# POEREG.net
KiCad netlist of a schematic drawn in EAGLE
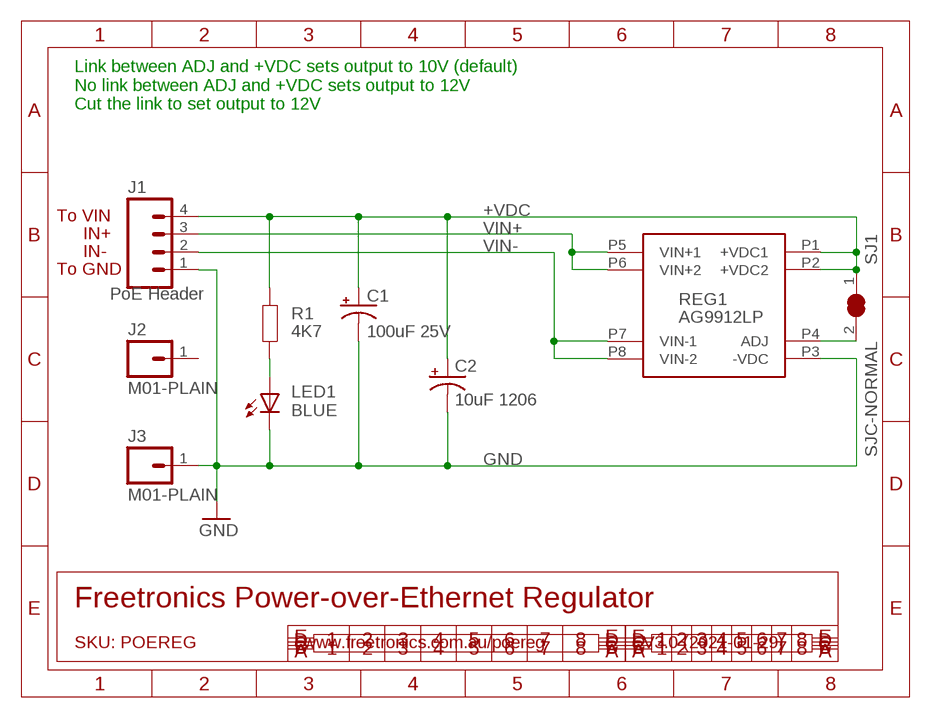
[diagram p0: schematic, sheet 1]

(export (version "E")
  (design (tool "Eeschema 10.0.6"))
  (components
    (comp (ref "C1")
      (value "100uF 25V")
      (footprint "eagle-import:PANASONIC_D")
      (libsource (lib "eagle-import") (part "CAP_POLD"))
    )
    (comp (ref "C2")
      (value "10uF 1206")
      (footprint "eagle-import:EIA3216")
      (libsource (lib "eagle-import") (part "CAP_POL1206"))
    )
    (comp (ref "J1")
      (value "PoE Header")
      (footprint "eagle-import:1X04")
      (libsource (lib "eagle-import") (part "M04-PLAIN"))
    )
    (comp (ref "J2")
      (value "M01-PLAIN")
      (footprint "eagle-import:1X01")
      (libsource (lib "eagle-import") (part "M01-PLAIN"))
    )
    (comp (ref "J3")
      (value "M01-PLAIN")
      (footprint "eagle-import:1X01")
      (libsource (lib "eagle-import") (part "M01-PLAIN"))
    )
    (comp (ref "LED1")
      (value "BLUE")
      (footprint "eagle-import:LED-0603")
      (libsource (lib "eagle-import") (part "LED0603"))
    )
    (comp (ref "R1")
      (value "4K7")
      (footprint "eagle-import:R0603")
      (libsource (lib "eagle-import") (part "RESISTOR0603"))
    )
    (comp (ref "REG1")
      (value "AG9912LP")
      (footprint "eagle-import:AG9900LP")
      (libsource (lib "eagle-import") (part "AG9900-LP"))
    )
    (comp (ref "SJ1")
      (value "SJC-NORMAL")
      (footprint "eagle-import:SJC")
      (libsource (lib "eagle-import") (part "SJC-NORMAL"))
    )
  )
  (nets
    (net (code "1") (name "/+VDC") (class "Default")
      (node (ref "C1") (pin "+") (pinfunction "+_+") (pintype "passive"))
      (node (ref "C2") (pin "A") (pinfunction "+_A") (pintype "passive"))
      (node (ref "J1") (pin "4") (pinfunction "4_4") (pintype "passive"))
      (node (ref "R1") (pin "1") (pinfunction "1_1") (pintype "passive"))
      (node (ref "REG1") (pin "P1") (pinfunction "+VDC1_P1") (pintype "bidirectional"))
      (node (ref "REG1") (pin "P2") (pinfunction "+VDC2_P2") (pintype "bidirectional"))
      (node (ref "SJ1") (pin "1") (pinfunction "1_1") (pintype "passive"))
    )
    (net (code "2") (name "/VIN+") (class "Default")
      (node (ref "J1") (pin "3") (pinfunction "3_3") (pintype "passive"))
      (node (ref "REG1") (pin "P5") (pinfunction "VIN+1_P5") (pintype "power_in"))
      (node (ref "REG1") (pin "P6") (pinfunction "VIN+2_P6") (pintype "power_in"))
    )
    (net (code "3") (name "/VIN-") (class "Default")
      (node (ref "J1") (pin "2") (pinfunction "2_2") (pintype "passive"))
      (node (ref "REG1") (pin "P7") (pinfunction "VIN-1_P7") (pintype "power_in"))
      (node (ref "REG1") (pin "P8") (pinfunction "VIN-2_P8") (pintype "power_in"))
    )
    (net (code "4") (name "GND") (class "Default")
      (node (ref "C1") (pin "-") (pinfunction "-_-") (pintype "passive"))
      (node (ref "C2") (pin "C") (pinfunction "-_C") (pintype "passive"))
      (node (ref "J1") (pin "1") (pinfunction "1_1") (pintype "passive"))
      (node (ref "J3") (pin "1") (pinfunction "1_1") (pintype "passive"))
      (node (ref "LED1") (pin "C") (pinfunction "C_C") (pintype "passive"))
      (node (ref "REG1") (pin "P3") (pinfunction "-VDC_P3") (pintype "bidirectional"))
    )
    (net (code "5") (name "Net-(LED1-PadA)") (class "Default")
      (node (ref "LED1") (pin "A") (pinfunction "A_A") (pintype "passive"))
      (node (ref "R1") (pin "2") (pinfunction "2_2") (pintype "passive"))
    )
    (net (code "6") (name "Net-(REG1-ADJ)") (class "Default")
      (node (ref "REG1") (pin "P4") (pinfunction "ADJ_P4") (pintype "input"))
      (node (ref "SJ1") (pin "2") (pinfunction "2_2") (pintype "passive"))
    )
    (net (code "7") (name "unconnected-(J2-Pad1)") (class "Default")
      (node (ref "J2") (pin "1") (pinfunction "1_1") (pintype "passive"))
    )
  )
)
